# FTDI_PROG3_eagle7x.net
KiCad netlist of a schematic drawn in EAGLE
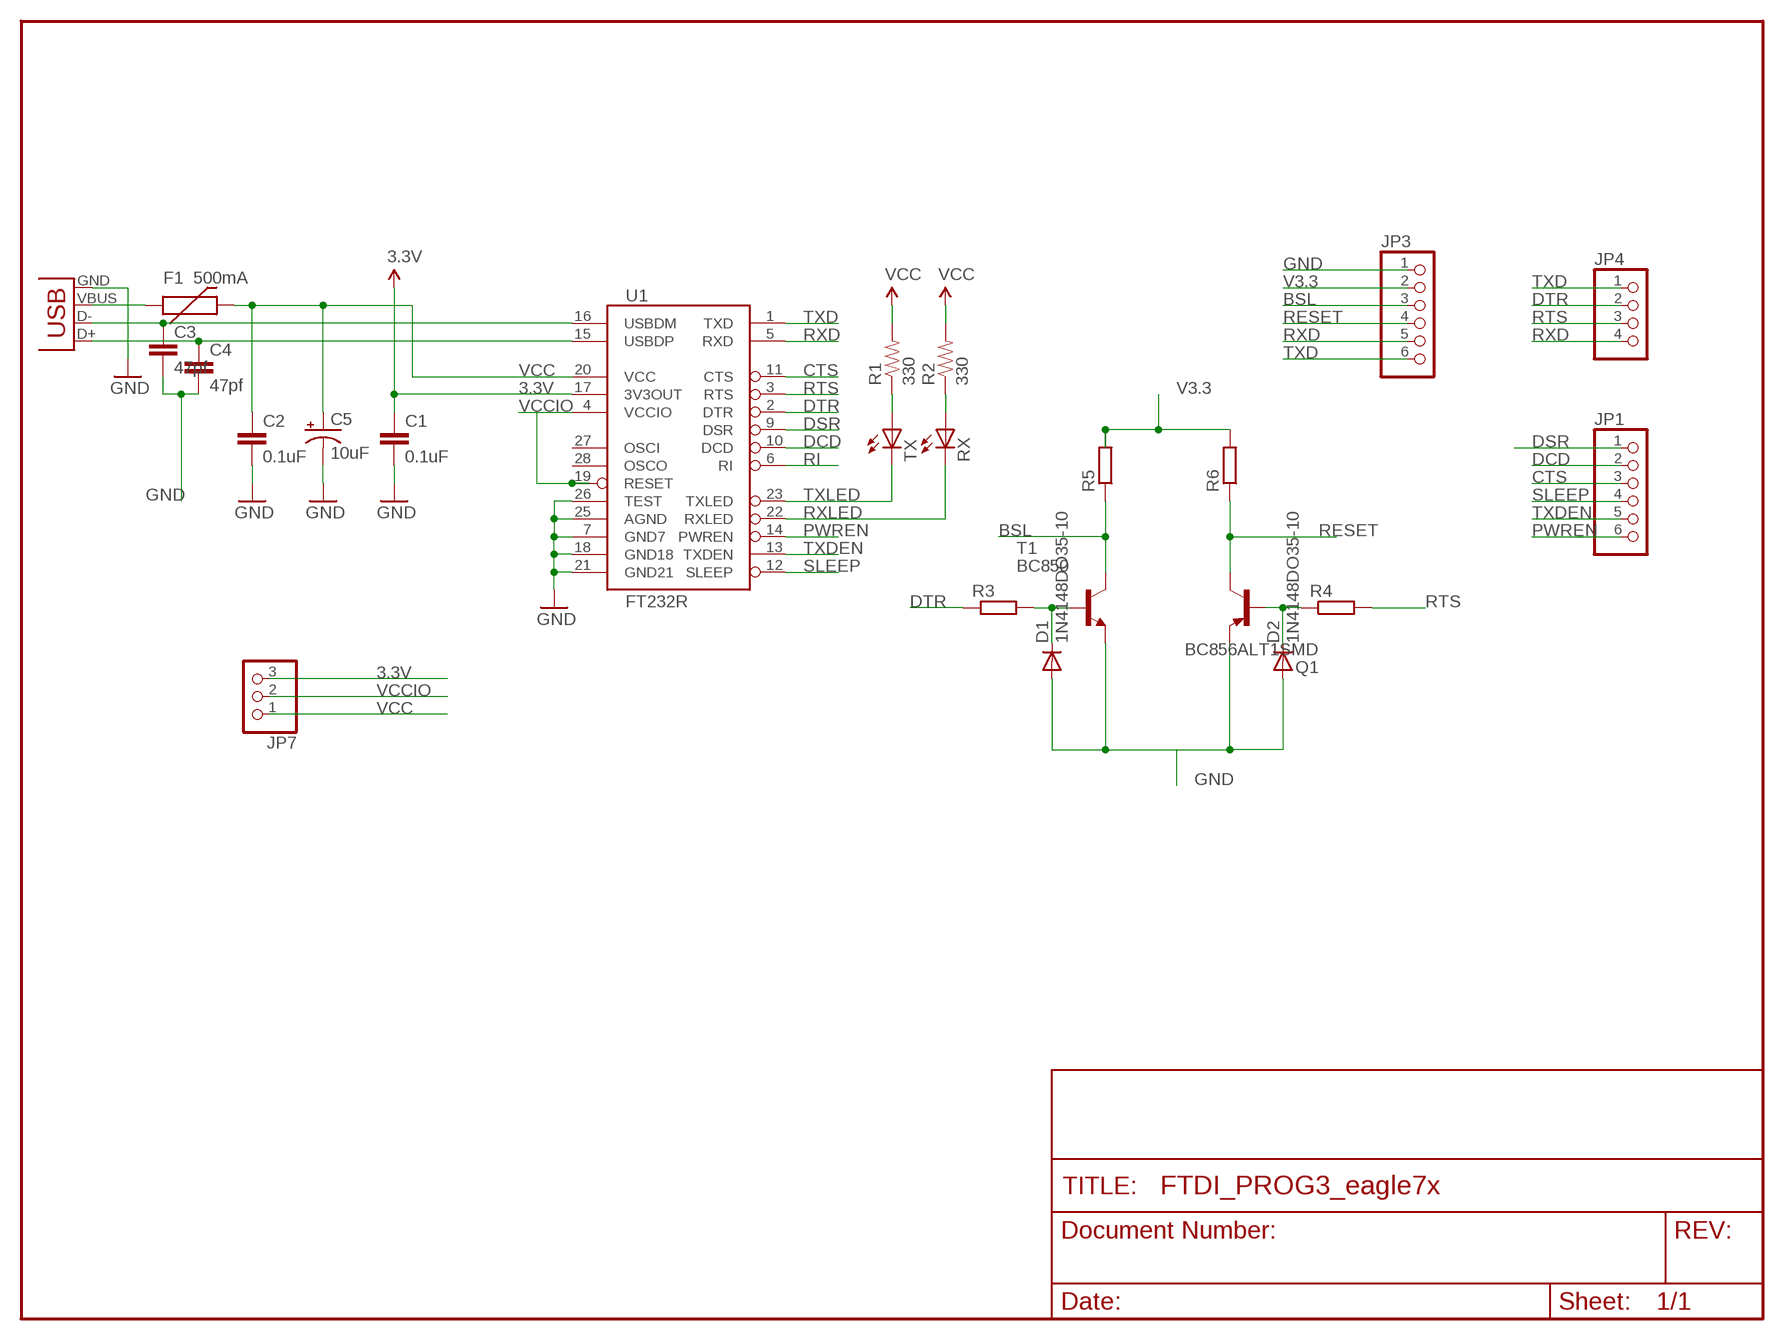
[diagram p0: schematic, sheet 1]

(export (version "E")
  (design (tool "Eeschema 10.0.6"))
  (components
    (comp (ref "C1")
      (value "0.1uF")
      (footprint "eagle-import:1206")
      (libsource (lib "eagle-import") (part "CAP1206"))
    )
    (comp (ref "C2")
      (value "0.1uF")
      (footprint "eagle-import:1206")
      (libsource (lib "eagle-import") (part "CAP1206"))
    )
    (comp (ref "C3")
      (value "47pf")
      (footprint "eagle-import:C025-024X044")
      (libsource (lib "eagle-import") (part "C-EU025-024X044"))
    )
    (comp (ref "C4")
      (value "47pf")
      (footprint "eagle-import:C025-025X050")
      (libsource (lib "eagle-import") (part "C-EU025-025X050"))
    )
    (comp (ref "C5")
      (value "10uF")
      (footprint "eagle-import:CPOL-RADIAL-100UF-25V")
      (libsource (lib "eagle-import") (part "CAP_POLPTH1"))
    )
    (comp (ref "D1")
      (value "1N4148DO35-10")
      (footprint "eagle-import:DO35-10")
      (libsource (lib "eagle-import") (part "1N4148DO35-10"))
    )
    (comp (ref "D2")
      (value "1N4148DO35-10")
      (footprint "eagle-import:DO35-10")
      (libsource (lib "eagle-import") (part "1N4148DO35-10"))
    )
    (comp (ref "F1")
      (value "500mA")
      (footprint "eagle-import:PTC-1206")
      (libsource (lib "eagle-import") (part "PTCSMD"))
    )
    (comp (ref "JP1")
      (value "PINHD-1X6")
      (footprint "eagle-import:1X06")
      (libsource (lib "eagle-import") (part "PINHD-1X6"))
    )
    (comp (ref "JP3")
      (value "PINHD-1X6")
      (footprint "eagle-import:1X06")
      (libsource (lib "eagle-import") (part "PINHD-1X6"))
    )
    (comp (ref "JP4")
      (value "PINHD-1X4")
      (footprint "eagle-import:1X04")
      (libsource (lib "eagle-import") (part "PINHD-1X4"))
    )
    (comp (ref "JP7")
      (value "PINHD-1X3")
      (footprint "eagle-import:1X03")
      (libsource (lib "eagle-import") (part "PINHD-1X3"))
    )
    (comp (ref "Q1")
      (value "BC856ALT1SMD")
      (footprint "eagle-import:SOT23-BEC")
      (libsource (lib "eagle-import") (part "BC856SMDALT1"))
    )
    (comp (ref "R1")
      (value "330")
      (footprint "eagle-import:1206")
      (libsource (lib "eagle-import") (part "RESISTOR1206"))
    )
    (comp (ref "R2")
      (value "330")
      (footprint "eagle-import:1206")
      (libsource (lib "eagle-import") (part "RESISTOR1206"))
    )
    (comp (ref "R3")
      (value "R-EU_0207/10")
      (footprint "eagle-import:0207_10")
      (libsource (lib "eagle-import") (part "R-EU_0207/10"))
    )
    (comp (ref "R4")
      (value "R-EU_0207/10")
      (footprint "eagle-import:0207_10")
      (libsource (lib "eagle-import") (part "R-EU_0207/10"))
    )
    (comp (ref "R5")
      (value "R-EU_0207/10")
      (footprint "eagle-import:0207_10")
      (libsource (lib "eagle-import") (part "R-EU_0207/10"))
    )
    (comp (ref "R6")
      (value "R-EU_0207/10")
      (footprint "eagle-import:0207_10")
      (libsource (lib "eagle-import") (part "R-EU_0207/10"))
    )
    (comp (ref "RX")
      (value "LED1206")
      (footprint "eagle-import:LED-1206")
      (libsource (lib "eagle-import") (part "LED1206"))
    )
    (comp (ref "T1")
      (value "BC850")
      (footprint "eagle-import:SOT23")
      (libsource (lib "eagle-import") (part "BC850"))
    )
    (comp (ref "TX")
      (value "LED1206")
      (footprint "eagle-import:LED-1206")
      (libsource (lib "eagle-import") (part "LED1206"))
    )
    (comp (ref "U1")
      (value "FT232R")
      (footprint "eagle-import:SSOP28DB")
      (libsource (lib "eagle-import") (part "FT232RLSSOP"))
    )
    (comp (ref "X2")
      (value "USBPTH")
      (footprint "eagle-import:USB-B-PTH")
      (libsource (lib "eagle-import") (part "USBPTH"))
    )
  )
  (nets
    (net (code "1") (name "/BSL") (class "Default")
      (node (ref "JP3") (pin "3") (pinfunction "3_3") (pintype "passive"))
      (node (ref "R5") (pin "1") (pinfunction "1_1") (pintype "passive"))
      (node (ref "T1") (pin "3") (pinfunction "C_3") (pintype "passive"))
    )
    (net (code "2") (name "/CTS") (class "Default")
      (node (ref "JP1") (pin "3") (pinfunction "3_3") (pintype "passive"))
      (node (ref "U1") (pin "11") (pinfunction "CTS_11") (pintype "input"))
    )
    (net (code "3") (name "/DCD") (class "Default")
      (node (ref "JP1") (pin "2") (pinfunction "2_2") (pintype "passive"))
      (node (ref "U1") (pin "10") (pinfunction "DCD_10") (pintype "input"))
    )
    (net (code "4") (name "/DSR") (class "Default")
      (node (ref "JP1") (pin "1") (pinfunction "1_1") (pintype "passive"))
      (node (ref "U1") (pin "9") (pinfunction "DSR_9") (pintype "input"))
    )
    (net (code "5") (name "/DTR") (class "Default")
      (node (ref "JP4") (pin "2") (pinfunction "2_2") (pintype "passive"))
      (node (ref "R3") (pin "1") (pinfunction "1_1") (pintype "passive"))
      (node (ref "U1") (pin "2") (pinfunction "DTR_2") (pintype "output"))
    )
    (net (code "6") (name "/PWREN") (class "Default")
      (node (ref "JP1") (pin "6") (pinfunction "6_6") (pintype "passive"))
      (node (ref "U1") (pin "14") (pinfunction "PWREN_14") (pintype "input"))
    )
    (net (code "7") (name "/RESET") (class "Default")
      (node (ref "JP3") (pin "4") (pinfunction "4_4") (pintype "passive"))
      (node (ref "Q1") (pin "C") (pinfunction "C_C") (pintype "passive"))
      (node (ref "R6") (pin "1") (pinfunction "1_1") (pintype "passive"))
    )
    (net (code "8") (name "/RI") (class "Default")
      (node (ref "U1") (pin "6") (pinfunction "RI_6") (pintype "input"))
    )
    (net (code "9") (name "/RTS") (class "Default")
      (node (ref "JP4") (pin "3") (pinfunction "3_3") (pintype "passive"))
      (node (ref "R4") (pin "2") (pinfunction "2_2") (pintype "passive"))
      (node (ref "U1") (pin "3") (pinfunction "RTS_3") (pintype "output"))
    )
    (net (code "10") (name "/RXD") (class "Default")
      (node (ref "JP3") (pin "5") (pinfunction "5_5") (pintype "passive"))
      (node (ref "JP4") (pin "4") (pinfunction "4_4") (pintype "passive"))
      (node (ref "U1") (pin "5") (pinfunction "RXD_5") (pintype "input"))
    )
    (net (code "11") (name "/RXLED") (class "Default")
      (node (ref "RX") (pin "C") (pinfunction "C_C") (pintype "passive"))
      (node (ref "U1") (pin "22") (pinfunction "RXLED_22") (pintype "input"))
    )
    (net (code "12") (name "/SLEEP") (class "Default")
      (node (ref "JP1") (pin "4") (pinfunction "4_4") (pintype "passive"))
      (node (ref "U1") (pin "12") (pinfunction "SLEEP_12") (pintype "input"))
    )
    (net (code "13") (name "/TXD") (class "Default")
      (node (ref "JP3") (pin "6") (pinfunction "6_6") (pintype "passive"))
      (node (ref "JP4") (pin "1") (pinfunction "1_1") (pintype "passive"))
      (node (ref "U1") (pin "1") (pinfunction "TXD_1") (pintype "output"))
    )
    (net (code "14") (name "/TXDEN") (class "Default")
      (node (ref "JP1") (pin "5") (pinfunction "5_5") (pintype "passive"))
      (node (ref "U1") (pin "13") (pinfunction "TXDEN_13") (pintype "input"))
    )
    (net (code "15") (name "/TXLED") (class "Default")
      (node (ref "TX") (pin "C") (pinfunction "C_C") (pintype "passive"))
      (node (ref "U1") (pin "23") (pinfunction "TXLED_23") (pintype "input"))
    )
    (net (code "16") (name "/V3.3") (class "Default")
      (node (ref "JP3") (pin "2") (pinfunction "2_2") (pintype "passive"))
      (node (ref "R5") (pin "2") (pinfunction "2_2") (pintype "passive"))
      (node (ref "R6") (pin "2") (pinfunction "2_2") (pintype "passive"))
    )
    (net (code "17") (name "/VCCIO") (class "Default")
      (node (ref "JP7") (pin "2") (pinfunction "2_2") (pintype "passive"))
      (node (ref "U1") (pin "19") (pinfunction "RESET_19") (pintype "input"))
      (node (ref "U1") (pin "4") (pinfunction "VCCIO_4") (pintype "power_in"))
    )
    (net (code "18") (name "3.3V") (class "Default")
      (node (ref "C1") (pin "1") (pinfunction "1_1") (pintype "passive"))
      (node (ref "JP7") (pin "3") (pinfunction "3_3") (pintype "passive"))
      (node (ref "U1") (pin "17") (pinfunction "3V3OUT_17") (pintype "output"))
    )
    (net (code "19") (name "GND") (class "Default")
      (node (ref "C1") (pin "2") (pinfunction "2_2") (pintype "passive"))
      (node (ref "C2") (pin "2") (pinfunction "2_2") (pintype "passive"))
      (node (ref "C3") (pin "2") (pinfunction "2_2") (pintype "passive"))
      (node (ref "C4") (pin "2") (pinfunction "2_2") (pintype "passive"))
      (node (ref "C5") (pin "2") (pinfunction "-_2") (pintype "passive"))
      (node (ref "D1") (pin "A") (pinfunction "A_A") (pintype "passive"))
      (node (ref "D2") (pin "A") (pinfunction "A_A") (pintype "passive"))
      (node (ref "JP3") (pin "1") (pinfunction "1_1") (pintype "passive"))
      (node (ref "Q1") (pin "E") (pinfunction "E_E") (pintype "passive"))
      (node (ref "T1") (pin "2") (pinfunction "E_2") (pintype "passive"))
      (node (ref "U1") (pin "18") (pinfunction "GND18_18") (pintype "power_in"))
      (node (ref "U1") (pin "21") (pinfunction "GND21_21") (pintype "power_in"))
      (node (ref "U1") (pin "25") (pinfunction "AGND_25") (pintype "power_in"))
      (node (ref "U1") (pin "26") (pinfunction "TEST_26") (pintype "input"))
      (node (ref "U1") (pin "7") (pinfunction "GND7_7") (pintype "power_in"))
      (node (ref "X2") (pin "GND") (pinfunction "GND_GND") (pintype "bidirectional"))
    )
    (net (code "20") (name "Net-(D2-PadC)") (class "Default")
      (node (ref "D2") (pin "C") (pinfunction "C_C") (pintype "passive"))
      (node (ref "Q1") (pin "B") (pinfunction "B_B") (pintype "passive"))
      (node (ref "R4") (pin "1") (pinfunction "1_1") (pintype "passive"))
    )
    (net (code "21") (name "Net-(F1-Pad1)") (class "Default")
      (node (ref "F1") (pin "1") (pinfunction "1_1") (pintype "bidirectional"))
      (node (ref "X2") (pin "VBUS") (pinfunction "VBUS_VBUS") (pintype "bidirectional"))
    )
    (net (code "22") (name "Net-(R1-Pad1)") (class "Default")
      (node (ref "R1") (pin "1") (pinfunction "1_1") (pintype "passive"))
      (node (ref "TX") (pin "A") (pinfunction "A_A") (pintype "passive"))
    )
    (net (code "23") (name "Net-(R2-Pad1)") (class "Default")
      (node (ref "R2") (pin "1") (pinfunction "1_1") (pintype "passive"))
      (node (ref "RX") (pin "A") (pinfunction "A_A") (pintype "passive"))
    )
    (net (code "24") (name "Net-(T1-B)") (class "Default")
      (node (ref "D1") (pin "C") (pinfunction "C_C") (pintype "passive"))
      (node (ref "R3") (pin "2") (pinfunction "2_2") (pintype "passive"))
      (node (ref "T1") (pin "1") (pinfunction "B_1") (pintype "passive"))
    )
    (net (code "25") (name "Net-(U1-USBDM)") (class "Default")
      (node (ref "C3") (pin "1") (pinfunction "1_1") (pintype "passive"))
      (node (ref "U1") (pin "16") (pinfunction "USBDM_16") (pintype "bidirectional"))
      (node (ref "X2") (pin "D-") (pinfunction "D-_D-") (pintype "bidirectional"))
    )
    (net (code "26") (name "Net-(U1-USBDP)") (class "Default")
      (node (ref "C4") (pin "1") (pinfunction "1_1") (pintype "passive"))
      (node (ref "U1") (pin "15") (pinfunction "USBDP_15") (pintype "bidirectional"))
      (node (ref "X2") (pin "D+") (pinfunction "D+_D+") (pintype "bidirectional"))
    )
    (net (code "27") (name "VCC") (class "Default")
      (node (ref "C2") (pin "1") (pinfunction "1_1") (pintype "passive"))
      (node (ref "C5") (pin "1") (pinfunction "+_1") (pintype "passive"))
      (node (ref "F1") (pin "2") (pinfunction "2_2") (pintype "bidirectional"))
      (node (ref "JP7") (pin "1") (pinfunction "1_1") (pintype "passive"))
      (node (ref "R1") (pin "2") (pinfunction "2_2") (pintype "passive"))
      (node (ref "R2") (pin "2") (pinfunction "2_2") (pintype "passive"))
      (node (ref "U1") (pin "20") (pinfunction "VCC_20") (pintype "power_in"))
    )
    (net (code "28") (name "unconnected-(U1-OSCI-Pad27)") (class "Default")
      (node (ref "U1") (pin "27") (pinfunction "OSCI_27") (pintype "input"))
    )
    (net (code "29") (name "unconnected-(U1-OSCO-Pad28)") (class "Default")
      (node (ref "U1") (pin "28") (pinfunction "OSCO_28") (pintype "output"))
    )
  )
)
